# STM32F103C8T6.net
KiCad netlist of a schematic drawn in EasyEDA Pro
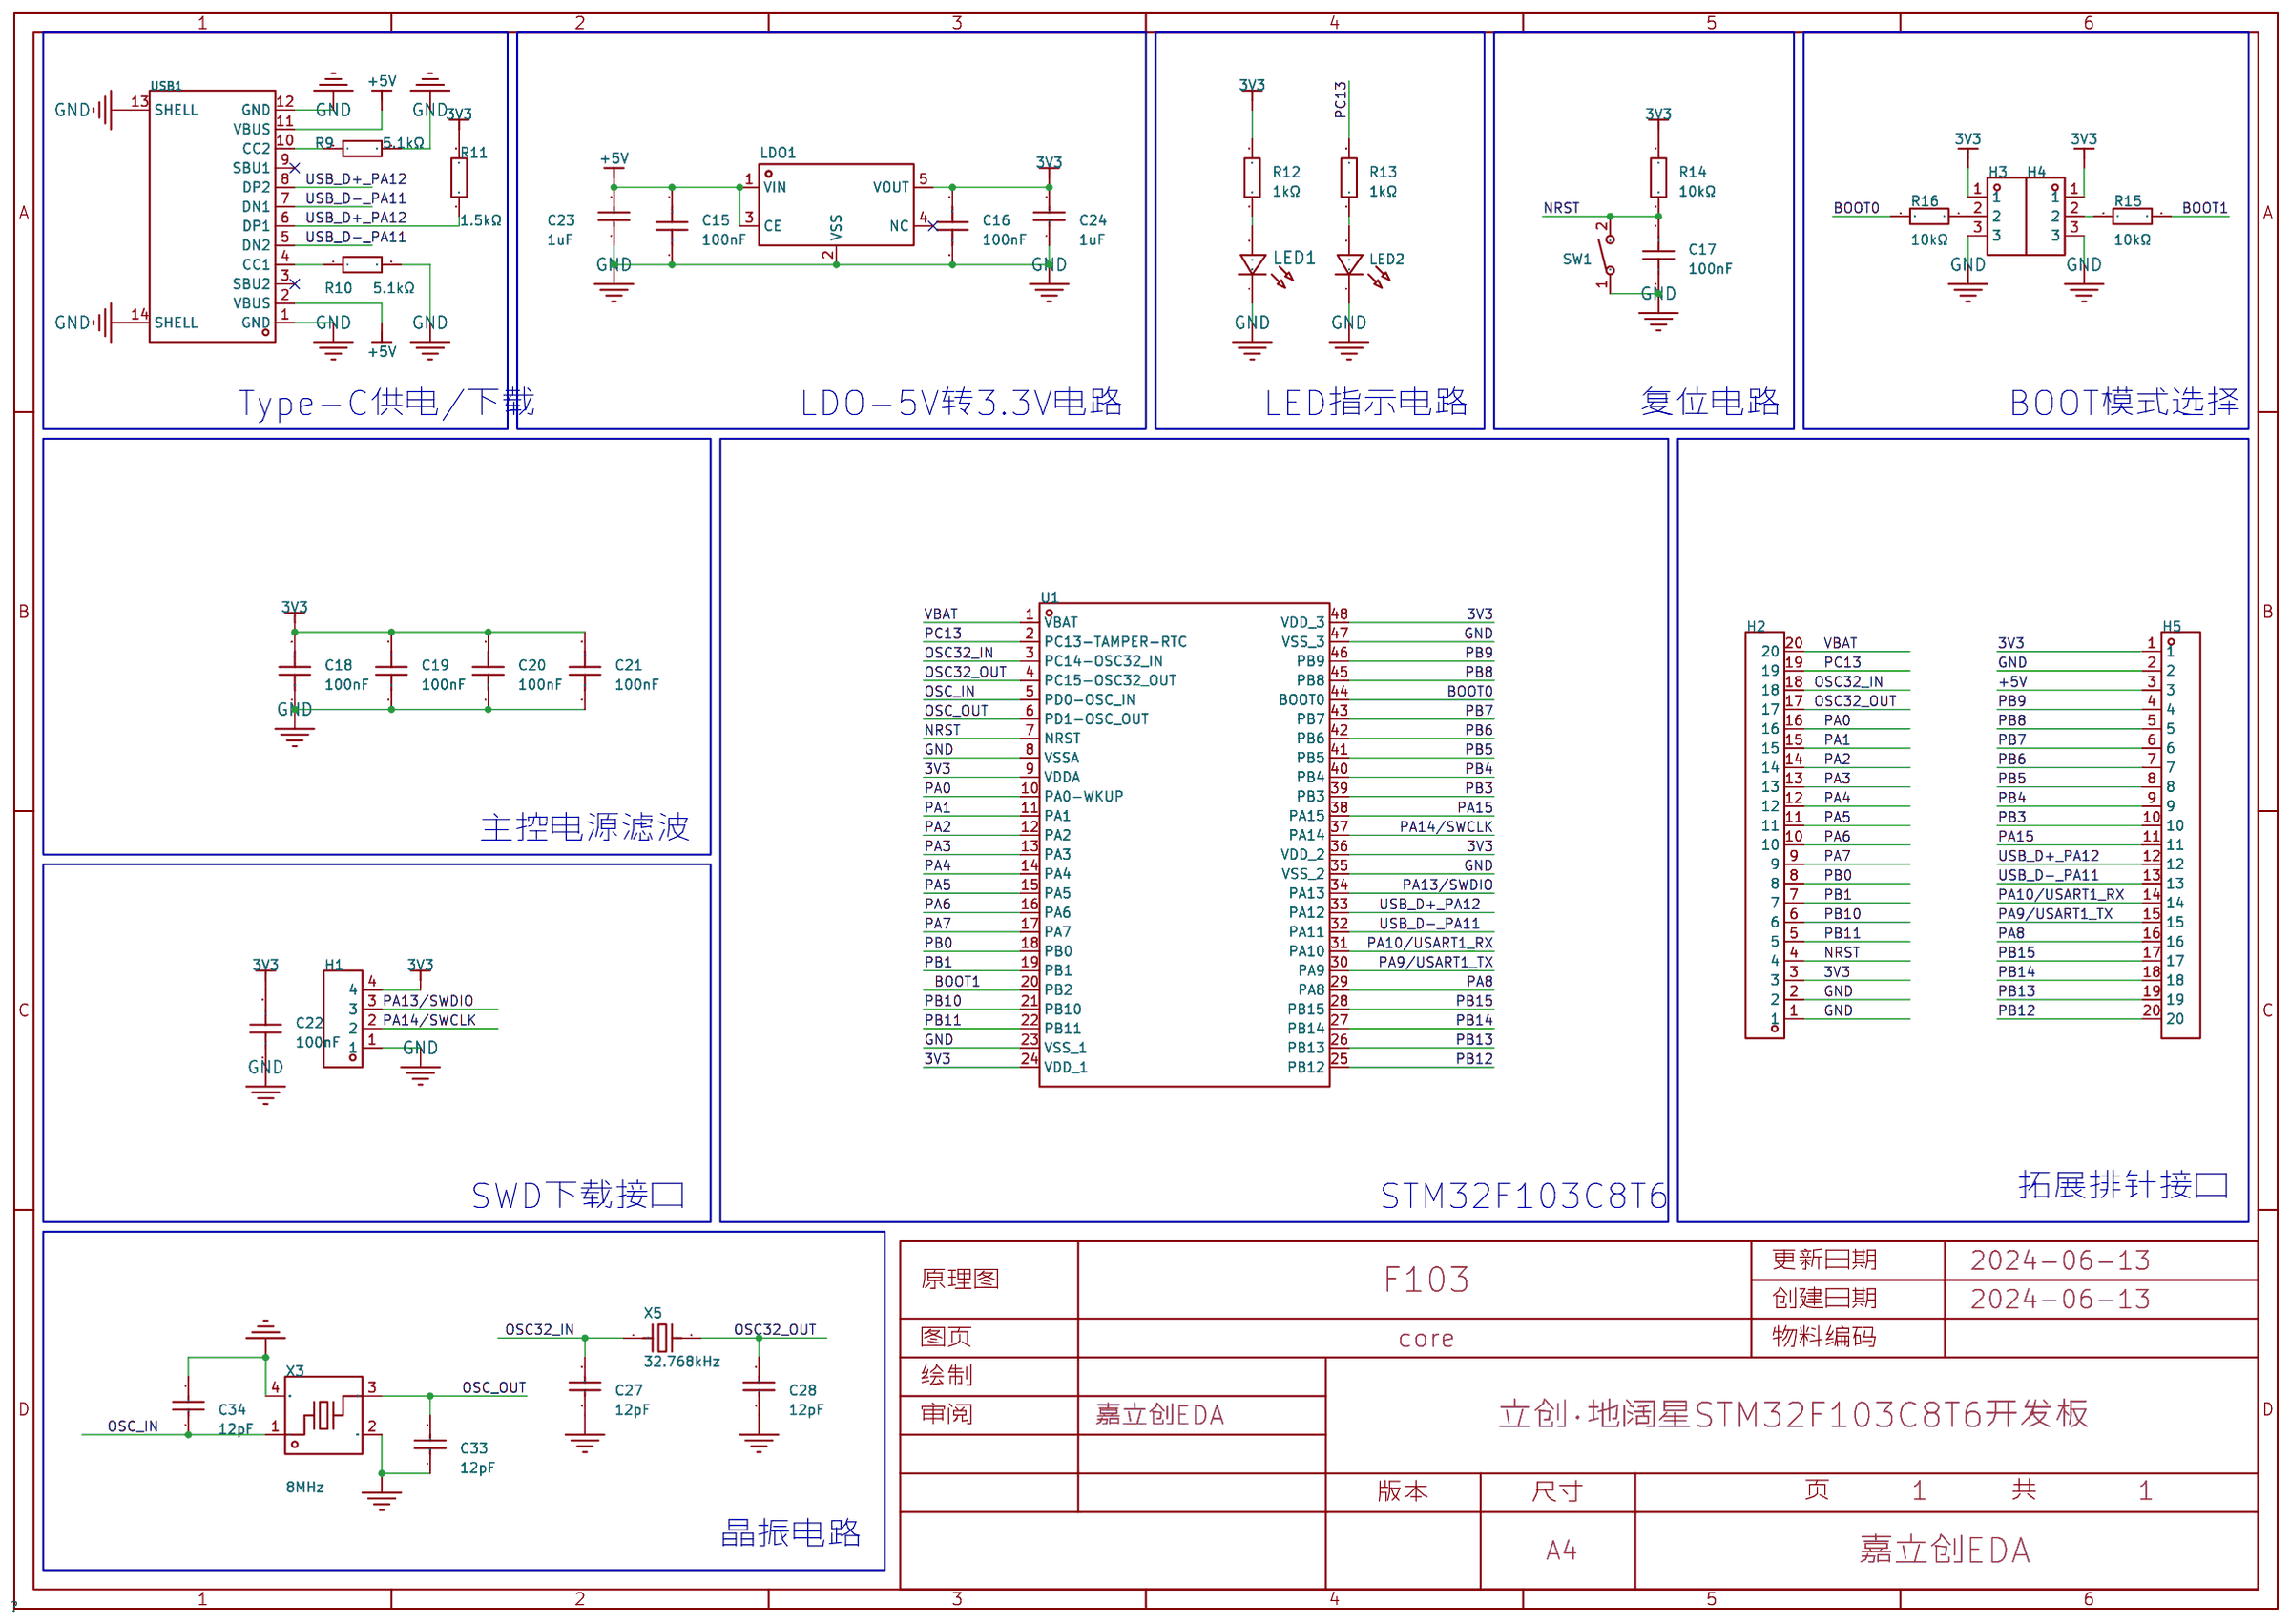
[diagram p0: schematic sheet]

(export (version "E")
  (design (tool "Eeschema 10.0.6"))
  (components
    (comp (ref "C15")
      (value "100nF")
      (footprint "easyedapro:C0402")
      (fields
        (field (name "Manufacturer Part") "GRM155R71H104KE14D")
        (field (name "Manufacturer") "muRata(村田)")
      )
      (libsource (lib "easyedapro") (part "GRM155R71H104KE14D"))
    )
    (comp (ref "C16")
      (value "100nF")
      (footprint "easyedapro:C0402")
      (fields
        (field (name "Manufacturer Part") "GRM155R71H104KE14D")
        (field (name "Manufacturer") "muRata(村田)")
      )
      (libsource (lib "easyedapro") (part "GRM155R71H104KE14D"))
    )
    (comp (ref "C17")
      (value "100nF")
      (footprint "easyedapro:C0402")
      (fields
        (field (name "Manufacturer Part") "GRM155R71H104KE14D")
        (field (name "Manufacturer") "muRata(村田)")
      )
      (libsource (lib "easyedapro") (part "GRM155R71H104KE14D"))
    )
    (comp (ref "C18")
      (value "100nF")
      (footprint "easyedapro:C0402")
      (fields
        (field (name "Manufacturer Part") "GRM155R71H104KE14D")
        (field (name "Manufacturer") "muRata(村田)")
      )
      (libsource (lib "easyedapro") (part "GRM155R71H104KE14D"))
    )
    (comp (ref "C19")
      (value "100nF")
      (footprint "easyedapro:C0402")
      (fields
        (field (name "Manufacturer Part") "GRM155R71H104KE14D")
        (field (name "Manufacturer") "muRata(村田)")
      )
      (libsource (lib "easyedapro") (part "GRM155R71H104KE14D"))
    )
    (comp (ref "C20")
      (value "100nF")
      (footprint "easyedapro:C0402")
      (fields
        (field (name "Manufacturer Part") "GRM155R71H104KE14D")
        (field (name "Manufacturer") "muRata(村田)")
      )
      (libsource (lib "easyedapro") (part "GRM155R71H104KE14D"))
    )
    (comp (ref "C21")
      (value "100nF")
      (footprint "easyedapro:C0402")
      (fields
        (field (name "Manufacturer Part") "GRM155R71H104KE14D")
        (field (name "Manufacturer") "muRata(村田)")
      )
      (libsource (lib "easyedapro") (part "GRM155R71H104KE14D"))
    )
    (comp (ref "C22")
      (value "100nF")
      (footprint "easyedapro:C0402")
      (fields
        (field (name "Manufacturer Part") "GRM155R71H104KE14D")
        (field (name "Manufacturer") "muRata(村田)")
      )
      (libsource (lib "easyedapro") (part "GRM155R71H104KE14D"))
    )
    (comp (ref "C23")
      (value "1uF")
      (footprint "easyedapro:C0402")
      (fields
        (field (name "Manufacturer Part") "CL05A105KP5NNNC")
        (field (name "Manufacturer") "SAMSUNG(三星)")
      )
      (libsource (lib "easyedapro") (part "CL05A105KP5NNNC"))
    )
    (comp (ref "C24")
      (value "1uF")
      (footprint "easyedapro:C0402")
      (fields
        (field (name "Manufacturer Part") "CL05A105KP5NNNC")
        (field (name "Manufacturer") "SAMSUNG(三星)")
      )
      (libsource (lib "easyedapro") (part "CL05A105KP5NNNC"))
    )
    (comp (ref "C27")
      (value "12pF")
      (footprint "easyedapro:C0402")
      (fields (field (name "Manufacturer Part") "0402CG120J500NT") (field (name "Manufacturer") "FH(风华)"))
      (libsource (lib "easyedapro") (part "0402CG120J500NT"))
    )
    (comp (ref "C28")
      (value "12pF")
      (footprint "easyedapro:C0402")
      (fields (field (name "Manufacturer Part") "0402CG120J500NT") (field (name "Manufacturer") "FH(风华)"))
      (libsource (lib "easyedapro") (part "0402CG120J500NT"))
    )
    (comp (ref "C33")
      (value "12pF")
      (footprint "easyedapro:C0402")
      (fields (field (name "Manufacturer Part") "0402CG120J500NT") (field (name "Manufacturer") "FH(风华)"))
      (libsource (lib "easyedapro") (part "0402CG120J500NT"))
    )
    (comp (ref "C34")
      (value "12pF")
      (footprint "easyedapro:C0402")
      (fields (field (name "Manufacturer Part") "0402CG120J500NT") (field (name "Manufacturer") "FH(风华)"))
      (libsource (lib "easyedapro") (part "0402CG120J500NT"))
    )
    (comp (ref "H1")
      (value "~")
      (footprint "easyedapro:HDR-TH_4P-P2.54-V-M")
      (libsource (lib "easyedapro") (part "PZ254V-11-04P"))
    )
    (comp (ref "H2")
      (value "~")
      (footprint "easyedapro:HDR-TH_20P-P2.54-V-M-1")
      (libsource (lib "easyedapro") (part "HDR_2.54-1x20P"))
    )
    (comp (ref "H3")
      (value "~")
      (footprint "easyedapro:HDR-TH_3P-P2.54-V-M")
      (libsource (lib "easyedapro") (part "PZ254V-11-03P_C2937625"))
    )
    (comp (ref "H4")
      (value "~")
      (footprint "easyedapro:HDR-TH_3P-P2.54-V-M")
      (libsource (lib "easyedapro") (part "PZ254V-11-03P_C2937625"))
    )
    (comp (ref "H5")
      (value "~")
      (footprint "easyedapro:HDR-TH_20P-P2.54-V-M-1")
      (libsource (lib "easyedapro") (part "HDR_2.54-1x20P"))
    )
    (comp (ref "LDO1")
      (value "ME6211C33M5G-N")
      (footprint "easyedapro:SOT-23-5_L3.0-W1.7-P0.95-LS2.8-BL")
      (fields (field (name "Manufacturer") "MICRONE(南京微盟)"))
      (libsource (lib "easyedapro") (part "ME6211C33M5G-N"))
    )
    (comp (ref "LED1")
      (value "~")
      (footprint "easyedapro:LED_0603")
      (libsource (lib "easyedapro") (part "LED_R"))
    )
    (comp (ref "LED2")
      (value "~")
      (footprint "easyedapro:LED_0603")
      (libsource (lib "easyedapro") (part "LED_B"))
    )
    (comp (ref "R9")
      (value "5.1kΩ")
      (footprint "easyedapro:R0402")
      (fields
        (field (name "Manufacturer Part") "0402WGF5101TCE")
        (field (name "Manufacturer") "UNI-ROYAL(厚声)")
      )
      (libsource (lib "easyedapro") (part "0402WGF5101TCE"))
    )
    (comp (ref "R10")
      (value "5.1kΩ")
      (footprint "easyedapro:R0402")
      (fields
        (field (name "Manufacturer Part") "0402WGF5101TCE")
        (field (name "Manufacturer") "UNI-ROYAL(厚声)")
      )
      (libsource (lib "easyedapro") (part "0402WGF5101TCE"))
    )
    (comp (ref "R11")
      (value "1.5kΩ")
      (footprint "easyedapro:R0402")
      (fields
        (field (name "Manufacturer Part") "0402WGF1501TCE")
        (field (name "Manufacturer") "UNI-ROYAL(厚声)")
      )
      (libsource (lib "easyedapro") (part "0402WGF1501TCE"))
    )
    (comp (ref "R12")
      (value "1kΩ")
      (footprint "easyedapro:R0402")
      (fields
        (field (name "Manufacturer Part") "0402WGF1001TCE")
        (field (name "Manufacturer") "UNI-ROYAL(厚声)")
      )
      (libsource (lib "easyedapro") (part "0402WGF1001TCE"))
    )
    (comp (ref "R13")
      (value "1kΩ")
      (footprint "easyedapro:R0402")
      (fields
        (field (name "Manufacturer Part") "0402WGF1001TCE")
        (field (name "Manufacturer") "UNI-ROYAL(厚声)")
      )
      (libsource (lib "easyedapro") (part "0402WGF1001TCE"))
    )
    (comp (ref "R14")
      (value "10kΩ")
      (footprint "easyedapro:R0402")
      (fields (field (name "Manufacturer Part") "RC0402FR-0710KL") (field (name "Manufacturer") "YAGEO(国巨)"))
      (libsource (lib "easyedapro") (part "RC0402FR-0710KL"))
    )
    (comp (ref "R15")
      (value "10kΩ")
      (footprint "easyedapro:R0402")
      (fields (field (name "Manufacturer Part") "RC0402FR-0710KL") (field (name "Manufacturer") "YAGEO(国巨)"))
      (libsource (lib "easyedapro") (part "RC0402FR-0710KL"))
    )
    (comp (ref "R16")
      (value "10kΩ")
      (footprint "easyedapro:R0402")
      (fields (field (name "Manufacturer Part") "RC0402FR-0710KL") (field (name "Manufacturer") "YAGEO(国巨)"))
      (libsource (lib "easyedapro") (part "RC0402FR-0710KL"))
    )
    (comp (ref "SW1")
      (value "TS-1101-B-W")
      (footprint "easyedapro:KEY-SMD_2P-L6.0-W3.6-P7.4-LS8.0-L")
      (fields (field (name "Manufacturer") "XKB Connectivity(中国星坤)"))
      (libsource (lib "easyedapro") (part "TS-1101-B-W"))
    )
    (comp (ref "U1")
      (value "STM32F103C8T6")
      (footprint "easyedapro:LQFP-48_L7.0-W7.0-P0.50-LS9.0-BL")
      (fields (field (name "Manufacturer") "ST(意法半导体)"))
      (libsource (lib "easyedapro") (part "STM32F103C8T6"))
    )
    (comp (ref "USB1")
      (value "TYPE-C 16PIN 2MD(073)")
      (footprint "easyedapro:USB-C-SMD_TYPE-C-6PIN-2MD-073")
      (fields (field (name "Manufacturer") "SHOU HAN(首韩)"))
      (libsource (lib "easyedapro") (part "TYPE-C 16PIN 2MD(073)"))
    )
    (comp (ref "X3")
      (value "8MHz")
      (footprint "easyedapro:CRYSTAL-SMD_4P-L3.2-W2.5-BL-1")
      (fields
        (field (name "Manufacturer Part") "XL2EL89COI-111YLC-8M")
        (field (name "Manufacturer") "YXC(扬兴晶振)")
      )
      (libsource (lib "easyedapro") (part "XL2EL89COI-111YLC-8M"))
    )
    (comp (ref "X5")
      (value "32.768kHz")
      (footprint "easyedapro:OSC-SMD_L3.2-W1.5")
      (fields (field (name "Manufacturer Part") "X321532768KGD2SI") (field (name "Manufacturer") "YXC(扬兴晶振)"))
      (libsource (lib "easyedapro") (part "X321532768KGD2SI"))
    )
  )
  (nets
    (net (code "1") (name "+5V") (class "Default")
      (node (ref "C15") (pin "2") (pinfunction "2_2") (pintype "unspecified"))
      (node (ref "C23") (pin "2") (pinfunction "2_2") (pintype "input"))
      (node (ref "H5") (pin "3") (pinfunction "3_3") (pintype "input"))
      (node (ref "LDO1") (pin "1") (pinfunction "VIN_1") (pintype "input"))
      (node (ref "LDO1") (pin "3") (pinfunction "CE_3") (pintype "input"))
      (node (ref "USB1") (pin "11") (pinfunction "VBUS_11") (pintype "input"))
      (node (ref "USB1") (pin "2") (pinfunction "VBUS_2") (pintype "input"))
    )
    (net (code "2") (name "/BOOT0") (class "Default")
      (node (ref "R16") (pin "2") (pinfunction "2_2") (pintype "input"))
      (node (ref "U1") (pin "44") (pinfunction "BOOT0_44") (pintype "unspecified"))
    )
    (net (code "3") (name "/BOOT1") (class "Default")
      (node (ref "R15") (pin "1") (pinfunction "1_1") (pintype "input"))
      (node (ref "U1") (pin "20") (pinfunction "PB2_20") (pintype "unspecified"))
    )
    (net (code "4") (name "/NRST") (class "Default")
      (node (ref "C17") (pin "2") (pinfunction "2_2") (pintype "unspecified"))
      (node (ref "H2") (pin "4") (pinfunction "4_4") (pintype "input"))
      (node (ref "R14") (pin "1") (pinfunction "1_1") (pintype "input"))
      (node (ref "SW1") (pin "2") (pinfunction "2_2") (pintype "input"))
      (node (ref "U1") (pin "7") (pinfunction "NRST_7") (pintype "unspecified"))
    )
    (net (code "5") (name "/OSC32_IN") (class "Default")
      (node (ref "C27") (pin "2") (pinfunction "2_2") (pintype "input"))
      (node (ref "H2") (pin "18") (pinfunction "18_18") (pintype "input"))
      (node (ref "U1") (pin "3") (pinfunction "PC14-OSC32_IN_3") (pintype "unspecified"))
      (node (ref "X5") (pin "1") (pinfunction "1_1") (pintype "input"))
    )
    (net (code "6") (name "/OSC32_OUT") (class "Default")
      (node (ref "C28") (pin "2") (pinfunction "2_2") (pintype "input"))
      (node (ref "H2") (pin "17") (pinfunction "17_17") (pintype "input"))
      (node (ref "U1") (pin "4") (pinfunction "PC15-OSC32_OUT_4") (pintype "unspecified"))
      (node (ref "X5") (pin "2") (pinfunction "2_2") (pintype "input"))
    )
    (net (code "7") (name "/OSC_IN") (class "Default")
      (node (ref "C34") (pin "1") (pinfunction "1_1") (pintype "input"))
      (node (ref "U1") (pin "5") (pinfunction "PD0-OSC_IN_5") (pintype "unspecified"))
      (node (ref "X3") (pin "1") (pinfunction "1_1") (pintype "input"))
    )
    (net (code "8") (name "/OSC_OUT") (class "Default")
      (node (ref "C33") (pin "2") (pinfunction "2_2") (pintype "input"))
      (node (ref "U1") (pin "6") (pinfunction "PD1-OSC_OUT_6") (pintype "unspecified"))
      (node (ref "X3") (pin "3") (pinfunction "3_3") (pintype "input"))
    )
    (net (code "9") (name "/PA0") (class "Default")
      (node (ref "H2") (pin "16") (pinfunction "16_16") (pintype "input"))
      (node (ref "U1") (pin "10") (pinfunction "PA0-WKUP_10") (pintype "unspecified"))
    )
    (net (code "10") (name "/PA1") (class "Default")
      (node (ref "H2") (pin "15") (pinfunction "15_15") (pintype "input"))
      (node (ref "U1") (pin "11") (pinfunction "PA1_11") (pintype "unspecified"))
    )
    (net (code "11") (name "/PA2") (class "Default")
      (node (ref "H2") (pin "14") (pinfunction "14_14") (pintype "input"))
      (node (ref "U1") (pin "12") (pinfunction "PA2_12") (pintype "unspecified"))
    )
    (net (code "12") (name "/PA3") (class "Default")
      (node (ref "H2") (pin "13") (pinfunction "13_13") (pintype "input"))
      (node (ref "U1") (pin "13") (pinfunction "PA3_13") (pintype "unspecified"))
    )
    (net (code "13") (name "/PA4") (class "Default")
      (node (ref "H2") (pin "12") (pinfunction "12_12") (pintype "input"))
      (node (ref "U1") (pin "14") (pinfunction "PA4_14") (pintype "unspecified"))
    )
    (net (code "14") (name "/PA5") (class "Default")
      (node (ref "H2") (pin "11") (pinfunction "11_11") (pintype "input"))
      (node (ref "U1") (pin "15") (pinfunction "PA5_15") (pintype "unspecified"))
    )
    (net (code "15") (name "/PA6") (class "Default")
      (node (ref "H2") (pin "10") (pinfunction "10_10") (pintype "input"))
      (node (ref "U1") (pin "16") (pinfunction "PA6_16") (pintype "unspecified"))
    )
    (net (code "16") (name "/PA7") (class "Default")
      (node (ref "H2") (pin "9") (pinfunction "9_9") (pintype "input"))
      (node (ref "U1") (pin "17") (pinfunction "PA7_17") (pintype "unspecified"))
    )
    (net (code "17") (name "/PA8") (class "Default")
      (node (ref "H5") (pin "16") (pinfunction "16_16") (pintype "input"))
      (node (ref "U1") (pin "29") (pinfunction "PA8_29") (pintype "unspecified"))
    )
    (net (code "18") (name "/PA9{slash}USART1_TX") (class "Default")
      (node (ref "H5") (pin "15") (pinfunction "15_15") (pintype "input"))
      (node (ref "U1") (pin "30") (pinfunction "PA9_30") (pintype "unspecified"))
    )
    (net (code "19") (name "/PA10{slash}USART1_RX") (class "Default")
      (node (ref "H5") (pin "14") (pinfunction "14_14") (pintype "input"))
      (node (ref "U1") (pin "31") (pinfunction "PA10_31") (pintype "unspecified"))
    )
    (net (code "20") (name "/PA13{slash}SWDIO") (class "Default")
      (node (ref "H1") (pin "3") (pinfunction "3_3") (pintype "input"))
      (node (ref "U1") (pin "34") (pinfunction "PA13_34") (pintype "unspecified"))
    )
    (net (code "21") (name "/PA14{slash}SWCLK") (class "Default")
      (node (ref "H1") (pin "2") (pinfunction "2_2") (pintype "input"))
      (node (ref "U1") (pin "37") (pinfunction "PA14_37") (pintype "unspecified"))
    )
    (net (code "22") (name "/PA15") (class "Default")
      (node (ref "H5") (pin "11") (pinfunction "11_11") (pintype "input"))
      (node (ref "U1") (pin "38") (pinfunction "PA15_38") (pintype "unspecified"))
    )
    (net (code "23") (name "/PB0") (class "Default")
      (node (ref "H2") (pin "8") (pinfunction "8_8") (pintype "input"))
      (node (ref "U1") (pin "18") (pinfunction "PB0_18") (pintype "unspecified"))
    )
    (net (code "24") (name "/PB1") (class "Default")
      (node (ref "H2") (pin "7") (pinfunction "7_7") (pintype "input"))
      (node (ref "U1") (pin "19") (pinfunction "PB1_19") (pintype "unspecified"))
    )
    (net (code "25") (name "/PB3") (class "Default")
      (node (ref "H5") (pin "10") (pinfunction "10_10") (pintype "input"))
      (node (ref "U1") (pin "39") (pinfunction "PB3_39") (pintype "unspecified"))
    )
    (net (code "26") (name "/PB4") (class "Default")
      (node (ref "H5") (pin "9") (pinfunction "9_9") (pintype "input"))
      (node (ref "U1") (pin "40") (pinfunction "PB4_40") (pintype "unspecified"))
    )
    (net (code "27") (name "/PB5") (class "Default")
      (node (ref "H5") (pin "8") (pinfunction "8_8") (pintype "input"))
      (node (ref "U1") (pin "41") (pinfunction "PB5_41") (pintype "unspecified"))
    )
    (net (code "28") (name "/PB6") (class "Default")
      (node (ref "H5") (pin "7") (pinfunction "7_7") (pintype "input"))
      (node (ref "U1") (pin "42") (pinfunction "PB6_42") (pintype "unspecified"))
    )
    (net (code "29") (name "/PB7") (class "Default")
      (node (ref "H5") (pin "6") (pinfunction "6_6") (pintype "input"))
      (node (ref "U1") (pin "43") (pinfunction "PB7_43") (pintype "unspecified"))
    )
    (net (code "30") (name "/PB8") (class "Default")
      (node (ref "H5") (pin "5") (pinfunction "5_5") (pintype "input"))
      (node (ref "U1") (pin "45") (pinfunction "PB8_45") (pintype "unspecified"))
    )
    (net (code "31") (name "/PB9") (class "Default")
      (node (ref "H5") (pin "4") (pinfunction "4_4") (pintype "input"))
      (node (ref "U1") (pin "46") (pinfunction "PB9_46") (pintype "unspecified"))
    )
    (net (code "32") (name "/PB10") (class "Default")
      (node (ref "H2") (pin "6") (pinfunction "6_6") (pintype "input"))
      (node (ref "U1") (pin "21") (pinfunction "PB10_21") (pintype "unspecified"))
    )
    (net (code "33") (name "/PB11") (class "Default")
      (node (ref "H2") (pin "5") (pinfunction "5_5") (pintype "input"))
      (node (ref "U1") (pin "22") (pinfunction "PB11_22") (pintype "unspecified"))
    )
    (net (code "34") (name "/PB12") (class "Default")
      (node (ref "H5") (pin "20") (pinfunction "20_20") (pintype "input"))
      (node (ref "U1") (pin "25") (pinfunction "PB12_25") (pintype "unspecified"))
    )
    (net (code "35") (name "/PB13") (class "Default")
      (node (ref "H5") (pin "19") (pinfunction "19_19") (pintype "input"))
      (node (ref "U1") (pin "26") (pinfunction "PB13_26") (pintype "unspecified"))
    )
    (net (code "36") (name "/PB14") (class "Default")
      (node (ref "H5") (pin "18") (pinfunction "18_18") (pintype "input"))
      (node (ref "U1") (pin "27") (pinfunction "PB14_27") (pintype "unspecified"))
    )
    (net (code "37") (name "/PB15") (class "Default")
      (node (ref "H5") (pin "17") (pinfunction "17_17") (pintype "input"))
      (node (ref "U1") (pin "28") (pinfunction "PB15_28") (pintype "unspecified"))
    )
    (net (code "38") (name "/PC13") (class "Default")
      (node (ref "H2") (pin "19") (pinfunction "19_19") (pintype "input"))
      (node (ref "R13") (pin "2") (pinfunction "2_2") (pintype "input"))
      (node (ref "U1") (pin "2") (pinfunction "PC13-TAMPER-RTC_2") (pintype "unspecified"))
    )
    (net (code "39") (name "/USB_D+_PA12") (class "Default")
      (node (ref "H5") (pin "12") (pinfunction "12_12") (pintype "input"))
      (node (ref "R11") (pin "1") (pinfunction "1_1") (pintype "input"))
      (node (ref "U1") (pin "33") (pinfunction "PA12_33") (pintype "unspecified"))
      (node (ref "USB1") (pin "6") (pinfunction "DP1_6") (pintype "input"))
      (node (ref "USB1") (pin "8") (pinfunction "DP2_8") (pintype "input"))
    )
    (net (code "40") (name "/USB_D-_PA11") (class "Default")
      (node (ref "H5") (pin "13") (pinfunction "13_13") (pintype "input"))
      (node (ref "U1") (pin "32") (pinfunction "PA11_32") (pintype "unspecified"))
      (node (ref "USB1") (pin "5") (pinfunction "DN2_5") (pintype "input"))
      (node (ref "USB1") (pin "7") (pinfunction "DN1_7") (pintype "input"))
    )
    (net (code "41") (name "/VBAT") (class "Default")
      (node (ref "H2") (pin "20") (pinfunction "20_20") (pintype "input"))
      (node (ref "U1") (pin "1") (pinfunction "VBAT_1") (pintype "unspecified"))
    )
    (net (code "42") (name "3V3") (class "Default")
      (node (ref "C16") (pin "2") (pinfunction "2_2") (pintype "unspecified"))
      (node (ref "C18") (pin "2") (pinfunction "2_2") (pintype "unspecified"))
      (node (ref "C19") (pin "2") (pinfunction "2_2") (pintype "unspecified"))
      (node (ref "C20") (pin "2") (pinfunction "2_2") (pintype "unspecified"))
      (node (ref "C21") (pin "2") (pinfunction "2_2") (pintype "unspecified"))
      (node (ref "C22") (pin "2") (pinfunction "2_2") (pintype "unspecified"))
      (node (ref "C24") (pin "2") (pinfunction "2_2") (pintype "input"))
      (node (ref "H1") (pin "4") (pinfunction "4_4") (pintype "input"))
      (node (ref "H2") (pin "3") (pinfunction "3_3") (pintype "input"))
      (node (ref "H3") (pin "1") (pinfunction "1_1") (pintype "input"))
      (node (ref "H4") (pin "1") (pinfunction "1_1") (pintype "input"))
      (node (ref "H5") (pin "1") (pinfunction "1_1") (pintype "input"))
      (node (ref "LDO1") (pin "5") (pinfunction "VOUT_5") (pintype "input"))
      (node (ref "R11") (pin "2") (pinfunction "2_2") (pintype "input"))
      (node (ref "R12") (pin "2") (pinfunction "2_2") (pintype "input"))
      (node (ref "R14") (pin "2") (pinfunction "2_2") (pintype "input"))
      (node (ref "U1") (pin "24") (pinfunction "VDD_1_24") (pintype "unspecified"))
      (node (ref "U1") (pin "36") (pinfunction "VDD_2_36") (pintype "unspecified"))
      (node (ref "U1") (pin "48") (pinfunction "VDD_3_48") (pintype "unspecified"))
      (node (ref "U1") (pin "9") (pinfunction "VDDA_9") (pintype "unspecified"))
    )
    (net (code "43") (name "GND") (class "Default")
      (node (ref "C15") (pin "1") (pinfunction "1_1") (pintype "unspecified"))
      (node (ref "C16") (pin "1") (pinfunction "1_1") (pintype "unspecified"))
      (node (ref "C17") (pin "1") (pinfunction "1_1") (pintype "unspecified"))
      (node (ref "C18") (pin "1") (pinfunction "1_1") (pintype "unspecified"))
      (node (ref "C19") (pin "1") (pinfunction "1_1") (pintype "unspecified"))
      (node (ref "C20") (pin "1") (pinfunction "1_1") (pintype "unspecified"))
      (node (ref "C21") (pin "1") (pinfunction "1_1") (pintype "unspecified"))
      (node (ref "C22") (pin "1") (pinfunction "1_1") (pintype "unspecified"))
      (node (ref "C23") (pin "1") (pinfunction "1_1") (pintype "input"))
      (node (ref "C24") (pin "1") (pinfunction "1_1") (pintype "input"))
      (node (ref "C27") (pin "1") (pinfunction "1_1") (pintype "input"))
      (node (ref "C28") (pin "1") (pinfunction "1_1") (pintype "input"))
      (node (ref "C33") (pin "1") (pinfunction "1_1") (pintype "input"))
      (node (ref "C34") (pin "2") (pinfunction "2_2") (pintype "input"))
      (node (ref "H1") (pin "1") (pinfunction "1_1") (pintype "input"))
      (node (ref "H2") (pin "1") (pinfunction "1_1") (pintype "input"))
      (node (ref "H2") (pin "2") (pinfunction "2_2") (pintype "input"))
      (node (ref "H3") (pin "3") (pinfunction "3_3") (pintype "input"))
      (node (ref "H4") (pin "3") (pinfunction "3_3") (pintype "input"))
      (node (ref "H5") (pin "2") (pinfunction "2_2") (pintype "input"))
      (node (ref "LDO1") (pin "2") (pinfunction "VSS_2") (pintype "input"))
      (node (ref "LED1") (pin "1") (pinfunction "C_1") (pintype "input"))
      (node (ref "LED2") (pin "1") (pinfunction "C_1") (pintype "input"))
      (node (ref "R10") (pin "2") (pinfunction "2_2") (pintype "input"))
      (node (ref "R9") (pin "2") (pinfunction "2_2") (pintype "input"))
      (node (ref "SW1") (pin "1") (pinfunction "1_1") (pintype "input"))
      (node (ref "U1") (pin "23") (pinfunction "VSS_1_23") (pintype "unspecified"))
      (node (ref "U1") (pin "35") (pinfunction "VSS_2_35") (pintype "unspecified"))
      (node (ref "U1") (pin "47") (pinfunction "VSS_3_47") (pintype "unspecified"))
      (node (ref "U1") (pin "8") (pinfunction "VSSA_8") (pintype "unspecified"))
      (node (ref "USB1") (pin "1") (pinfunction "GND_1") (pintype "input"))
      (node (ref "USB1") (pin "12") (pinfunction "GND_12") (pintype "input"))
      (node (ref "USB1") (pin "13") (pinfunction "SHELL_13") (pintype "input"))
      (node (ref "USB1") (pin "14") (pinfunction "SHELL_14") (pintype "input"))
      (node (ref "X3") (pin "2") (pinfunction "GND_2") (pintype "input"))
      (node (ref "X3") (pin "4") (pinfunction "GND_4") (pintype "input"))
    )
    (net (code "44") (name "Net-(H3-Pad2)") (class "Default")
      (node (ref "H3") (pin "2") (pinfunction "2_2") (pintype "input"))
      (node (ref "R16") (pin "1") (pinfunction "1_1") (pintype "input"))
    )
    (net (code "45") (name "Net-(H4-Pad2)") (class "Default")
      (node (ref "H4") (pin "2") (pinfunction "2_2") (pintype "input"))
      (node (ref "R15") (pin "2") (pinfunction "2_2") (pintype "input"))
    )
    (net (code "46") (name "Net-(LED1-A)") (class "Default")
      (node (ref "LED1") (pin "2") (pinfunction "A_2") (pintype "input"))
      (node (ref "R12") (pin "1") (pinfunction "1_1") (pintype "input"))
    )
    (net (code "47") (name "Net-(LED2-A)") (class "Default")
      (node (ref "LED2") (pin "2") (pinfunction "A_2") (pintype "input"))
      (node (ref "R13") (pin "1") (pinfunction "1_1") (pintype "input"))
    )
    (net (code "48") (name "Net-(USB1-CC1)") (class "Default")
      (node (ref "R10") (pin "1") (pinfunction "1_1") (pintype "input"))
      (node (ref "USB1") (pin "4") (pinfunction "CC1_4") (pintype "input"))
    )
    (net (code "49") (name "Net-(USB1-CC2)") (class "Default")
      (node (ref "R9") (pin "1") (pinfunction "1_1") (pintype "input"))
      (node (ref "USB1") (pin "10") (pinfunction "CC2_10") (pintype "input"))
    )
    (net (code "50") (name "unconnected-(LDO1-NC-Pad4)") (class "Default")
      (node (ref "LDO1") (pin "4") (pinfunction "NC_4") (pintype "input+no_connect"))
    )
    (net (code "51") (name "unconnected-(USB1-SBU1-Pad9)") (class "Default")
      (node (ref "USB1") (pin "9") (pinfunction "SBU1_9") (pintype "input+no_connect"))
    )
    (net (code "52") (name "unconnected-(USB1-SBU2-Pad3)") (class "Default")
      (node (ref "USB1") (pin "3") (pinfunction "SBU2_3") (pintype "input+no_connect"))
    )
  )
)
